# cable-adapter-24.net
KiCad netlist of a schematic drawn in EAGLE
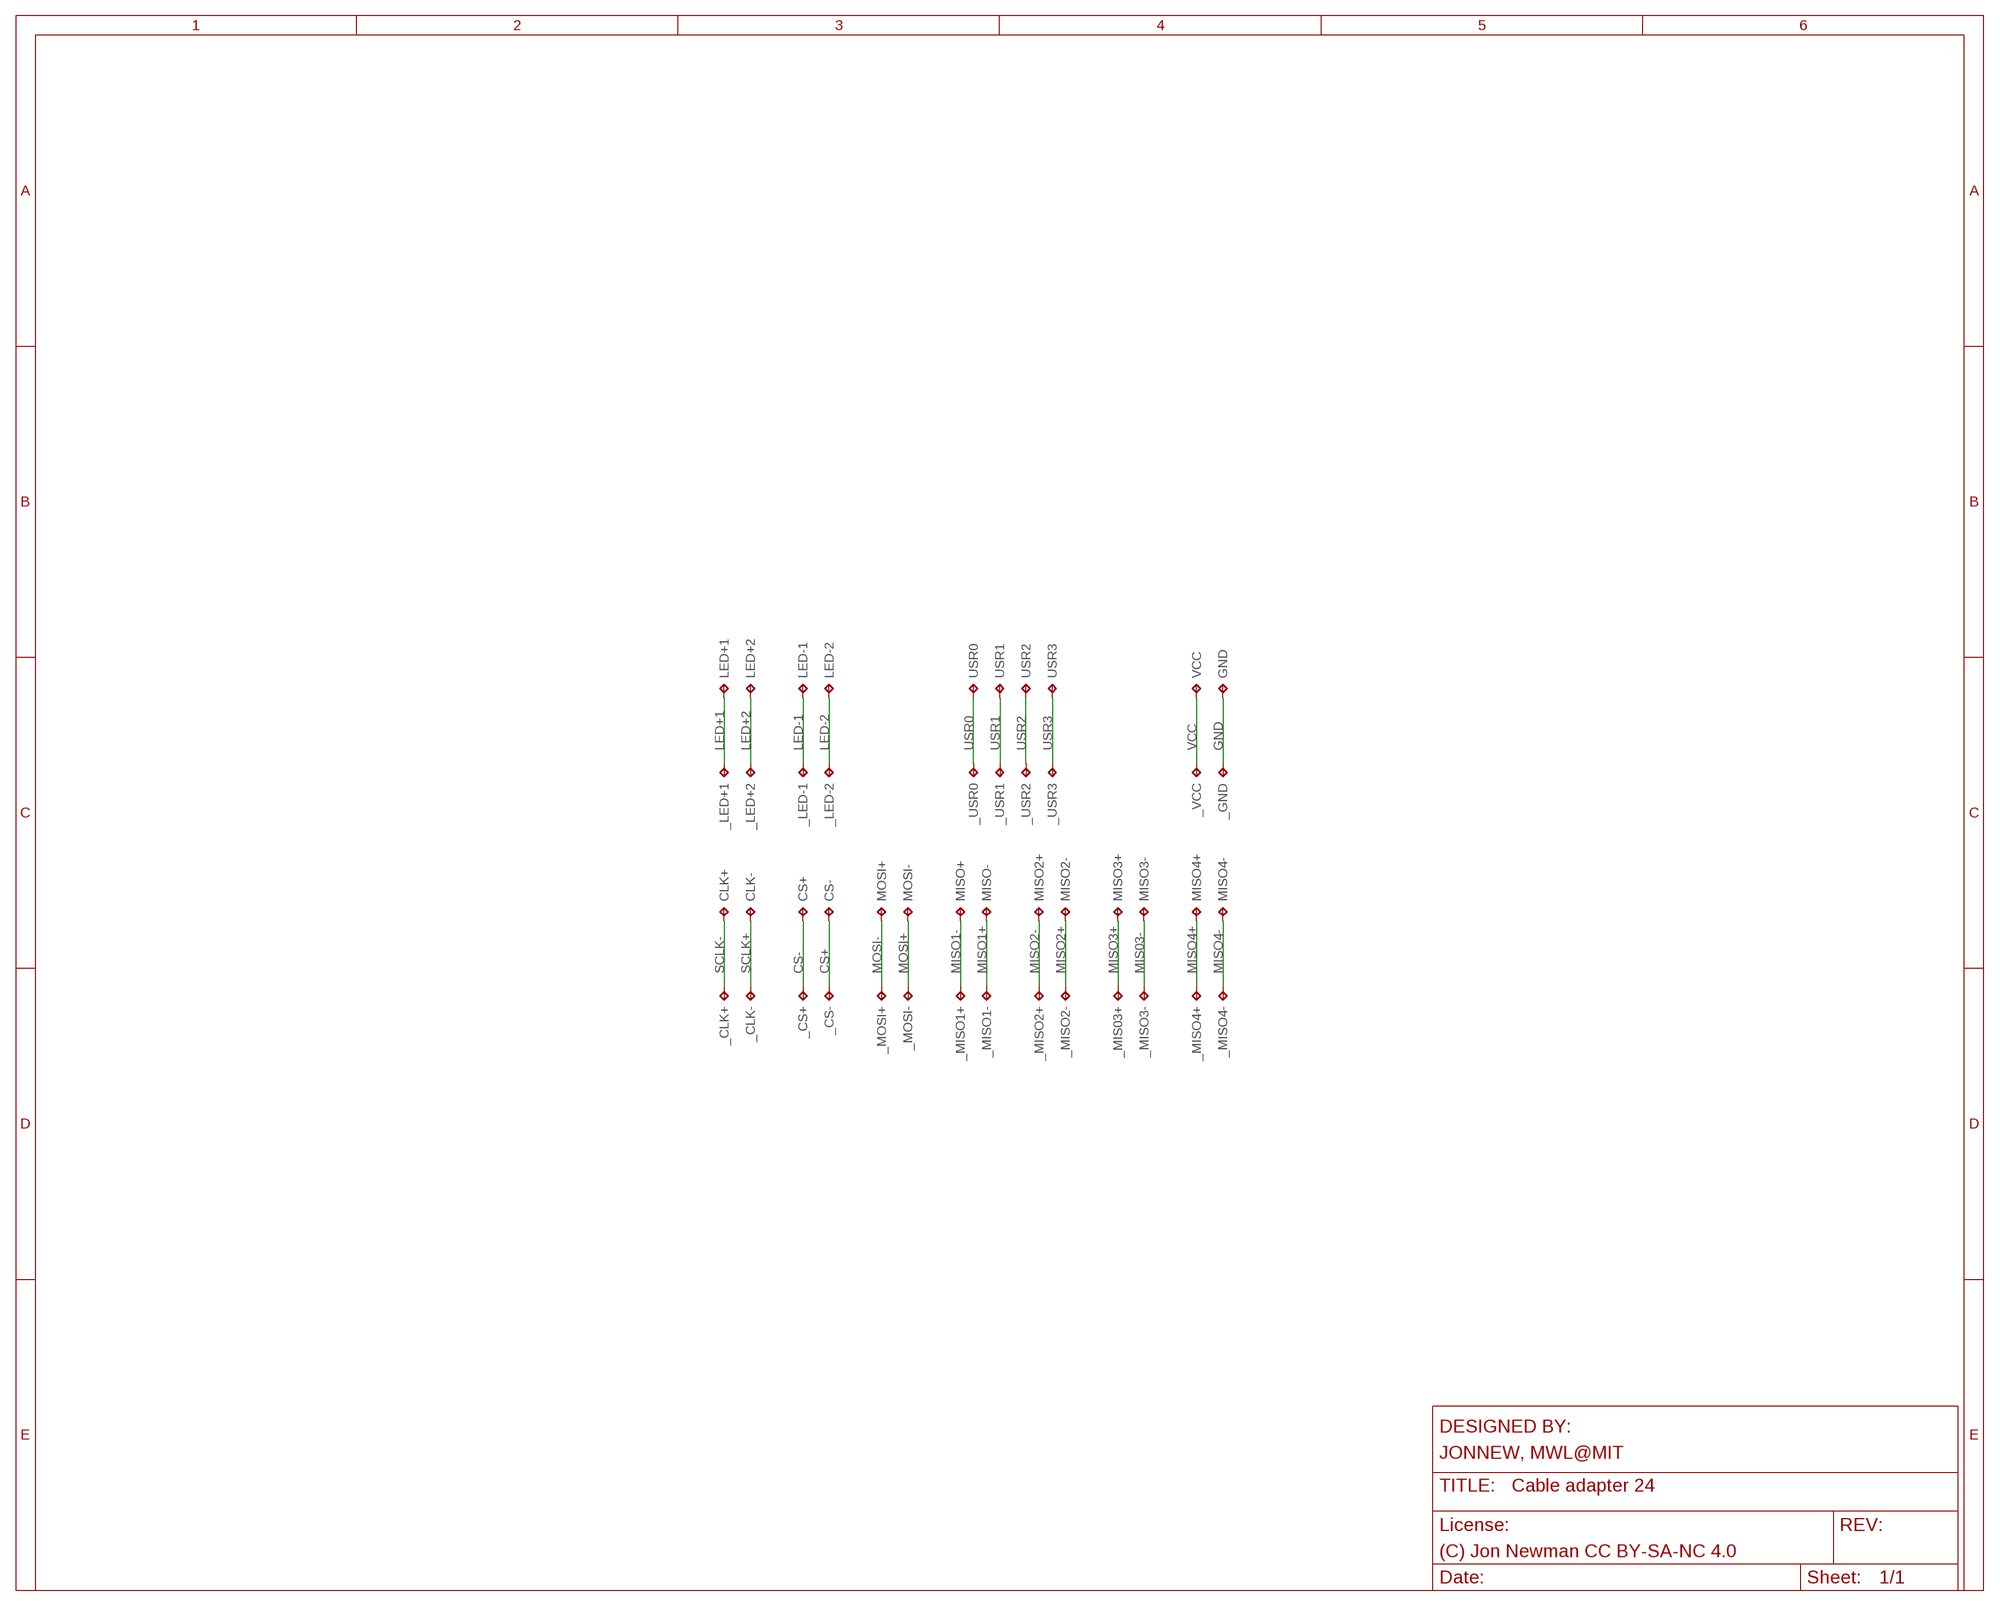
[diagram p0: schematic, sheet 1]

(export (version "E")
  (design (tool "Eeschema 10.0.6"))
  (components
    (comp (ref "CLK+")
      (value "TP_SPI_WIRE+")
      (footprint "eagle-import:SPI_WIRE+")
      (libsource (lib "eagle-import") (part "TP_SPI_WIRE+"))
    )
    (comp (ref "CLK-")
      (value "TP_SPI_WIRE+")
      (footprint "eagle-import:SPI_WIRE+")
      (libsource (lib "eagle-import") (part "TP_SPI_WIRE+"))
    )
    (comp (ref "CS+")
      (value "TP_SPI_WIRE+")
      (footprint "eagle-import:SPI_WIRE+")
      (libsource (lib "eagle-import") (part "TP_SPI_WIRE+"))
    )
    (comp (ref "CS-")
      (value "TP_SPI_WIRE+")
      (footprint "eagle-import:SPI_WIRE+")
      (libsource (lib "eagle-import") (part "TP_SPI_WIRE+"))
    )
    (comp (ref "GND")
      (value "TP_SPI_WIRE+")
      (footprint "eagle-import:SPI_WIRE+")
      (libsource (lib "eagle-import") (part "TP_SPI_WIRE+"))
    )
    (comp (ref "LED+1")
      (value "TP_SPI_WIRE+")
      (footprint "eagle-import:SPI_WIRE+")
      (libsource (lib "eagle-import") (part "TP_SPI_WIRE+"))
    )
    (comp (ref "LED+2")
      (value "TP_SPI_WIRE+")
      (footprint "eagle-import:SPI_WIRE+")
      (libsource (lib "eagle-import") (part "TP_SPI_WIRE+"))
    )
    (comp (ref "LED-1")
      (value "TP_SPI_WIRE+")
      (footprint "eagle-import:SPI_WIRE+")
      (libsource (lib "eagle-import") (part "TP_SPI_WIRE+"))
    )
    (comp (ref "LED-2")
      (value "TP_SPI_WIRE+")
      (footprint "eagle-import:SPI_WIRE+")
      (libsource (lib "eagle-import") (part "TP_SPI_WIRE+"))
    )
    (comp (ref "MISO+")
      (value "TP_SPI_WIRE+")
      (footprint "eagle-import:SPI_WIRE+")
      (libsource (lib "eagle-import") (part "TP_SPI_WIRE+"))
    )
    (comp (ref "MISO-")
      (value "TP_SPI_WIRE+")
      (footprint "eagle-import:SPI_WIRE+")
      (libsource (lib "eagle-import") (part "TP_SPI_WIRE+"))
    )
    (comp (ref "MISO2+")
      (value "TP_SPI_WIRE+")
      (footprint "eagle-import:SPI_WIRE+")
      (libsource (lib "eagle-import") (part "TP_SPI_WIRE+"))
    )
    (comp (ref "MISO2-")
      (value "TP_SPI_WIRE+")
      (footprint "eagle-import:SPI_WIRE+")
      (libsource (lib "eagle-import") (part "TP_SPI_WIRE+"))
    )
    (comp (ref "MISO3+")
      (value "TP_SPI_WIRE+")
      (footprint "eagle-import:SPI_WIRE+")
      (libsource (lib "eagle-import") (part "TP_SPI_WIRE+"))
    )
    (comp (ref "MISO3-")
      (value "TP_SPI_WIRE+")
      (footprint "eagle-import:SPI_WIRE+")
      (libsource (lib "eagle-import") (part "TP_SPI_WIRE+"))
    )
    (comp (ref "MISO4+")
      (value "TP_SPI_WIRE+")
      (footprint "eagle-import:SPI_WIRE+")
      (libsource (lib "eagle-import") (part "TP_SPI_WIRE+"))
    )
    (comp (ref "MISO4-")
      (value "TP_SPI_WIRE+")
      (footprint "eagle-import:SPI_WIRE+")
      (libsource (lib "eagle-import") (part "TP_SPI_WIRE+"))
    )
    (comp (ref "MOSI+")
      (value "TP_SPI_WIRE+")
      (footprint "eagle-import:SPI_WIRE+")
      (libsource (lib "eagle-import") (part "TP_SPI_WIRE+"))
    )
    (comp (ref "MOSI-")
      (value "TP_SPI_WIRE+")
      (footprint "eagle-import:SPI_WIRE+")
      (libsource (lib "eagle-import") (part "TP_SPI_WIRE+"))
    )
    (comp (ref "USR0")
      (value "TP_SPI_WIRE+")
      (footprint "eagle-import:SPI_WIRE+")
      (libsource (lib "eagle-import") (part "TP_SPI_WIRE+"))
    )
    (comp (ref "USR1")
      (value "TP_SPI_WIRE+")
      (footprint "eagle-import:SPI_WIRE+")
      (libsource (lib "eagle-import") (part "TP_SPI_WIRE+"))
    )
    (comp (ref "USR2")
      (value "TP_SPI_WIRE+")
      (footprint "eagle-import:SPI_WIRE+")
      (libsource (lib "eagle-import") (part "TP_SPI_WIRE+"))
    )
    (comp (ref "USR3")
      (value "TP_SPI_WIRE+")
      (footprint "eagle-import:SPI_WIRE+")
      (libsource (lib "eagle-import") (part "TP_SPI_WIRE+"))
    )
    (comp (ref "VCC")
      (value "TP_SPI_WIRE+")
      (footprint "eagle-import:SPI_WIRE+")
      (libsource (lib "eagle-import") (part "TP_SPI_WIRE+"))
    )
    (comp (ref "_CLK+")
      (value "TP_SPI_WIRE+")
      (footprint "eagle-import:SPI_WIRE+")
      (libsource (lib "eagle-import") (part "TP_SPI_WIRE+"))
    )
    (comp (ref "_CLK-")
      (value "TP_SPI_WIRE+")
      (footprint "eagle-import:SPI_WIRE+")
      (libsource (lib "eagle-import") (part "TP_SPI_WIRE+"))
    )
    (comp (ref "_CS+")
      (value "TP_SPI_WIRE+")
      (footprint "eagle-import:SPI_WIRE+")
      (libsource (lib "eagle-import") (part "TP_SPI_WIRE+"))
    )
    (comp (ref "_CS-")
      (value "TP_SPI_WIRE+")
      (footprint "eagle-import:SPI_WIRE+")
      (libsource (lib "eagle-import") (part "TP_SPI_WIRE+"))
    )
    (comp (ref "_GND")
      (value "TP_SPI_WIRE+")
      (footprint "eagle-import:SPI_WIRE+")
      (libsource (lib "eagle-import") (part "TP_SPI_WIRE+"))
    )
    (comp (ref "_LED+1")
      (value "TP_SPI_WIRE+")
      (footprint "eagle-import:SPI_WIRE+")
      (libsource (lib "eagle-import") (part "TP_SPI_WIRE+"))
    )
    (comp (ref "_LED+2")
      (value "TP_SPI_WIRE+")
      (footprint "eagle-import:SPI_WIRE+")
      (libsource (lib "eagle-import") (part "TP_SPI_WIRE+"))
    )
    (comp (ref "_LED-1")
      (value "TP_SPI_WIRE+")
      (footprint "eagle-import:SPI_WIRE+")
      (libsource (lib "eagle-import") (part "TP_SPI_WIRE+"))
    )
    (comp (ref "_LED-2")
      (value "TP_SPI_WIRE+")
      (footprint "eagle-import:SPI_WIRE+")
      (libsource (lib "eagle-import") (part "TP_SPI_WIRE+"))
    )
    (comp (ref "_MIS03+")
      (value "TP_SPI_WIRE+")
      (footprint "eagle-import:SPI_WIRE+")
      (libsource (lib "eagle-import") (part "TP_SPI_WIRE+"))
    )
    (comp (ref "_MISO1+")
      (value "TP_SPI_WIRE+")
      (footprint "eagle-import:SPI_WIRE+")
      (libsource (lib "eagle-import") (part "TP_SPI_WIRE+"))
    )
    (comp (ref "_MISO1-")
      (value "TP_SPI_WIRE+")
      (footprint "eagle-import:SPI_WIRE+")
      (libsource (lib "eagle-import") (part "TP_SPI_WIRE+"))
    )
    (comp (ref "_MISO2+")
      (value "TP_SPI_WIRE+")
      (footprint "eagle-import:SPI_WIRE+")
      (libsource (lib "eagle-import") (part "TP_SPI_WIRE+"))
    )
    (comp (ref "_MISO2-")
      (value "TP_SPI_WIRE+")
      (footprint "eagle-import:SPI_WIRE+")
      (libsource (lib "eagle-import") (part "TP_SPI_WIRE+"))
    )
    (comp (ref "_MISO3-")
      (value "MISO3+")
      (footprint "eagle-import:SPI_WIRE+")
      (libsource (lib "eagle-import") (part "TP_SPI_WIRE+"))
    )
    (comp (ref "_MISO4+")
      (value "TP_SPI_WIRE+")
      (footprint "eagle-import:SPI_WIRE+")
      (libsource (lib "eagle-import") (part "TP_SPI_WIRE+"))
    )
    (comp (ref "_MISO4-")
      (value "TP_SPI_WIRE+")
      (footprint "eagle-import:SPI_WIRE+")
      (libsource (lib "eagle-import") (part "TP_SPI_WIRE+"))
    )
    (comp (ref "_MOSI+")
      (value "TP_SPI_WIRE+")
      (footprint "eagle-import:SPI_WIRE+")
      (libsource (lib "eagle-import") (part "TP_SPI_WIRE+"))
    )
    (comp (ref "_MOSI-")
      (value "TP_SPI_WIRE+")
      (footprint "eagle-import:SPI_WIRE+")
      (libsource (lib "eagle-import") (part "TP_SPI_WIRE+"))
    )
    (comp (ref "_USR0")
      (value "TP_SPI_WIRE+")
      (footprint "eagle-import:SPI_WIRE+")
      (libsource (lib "eagle-import") (part "TP_SPI_WIRE+"))
    )
    (comp (ref "_USR1")
      (value "TP_SPI_WIRE+")
      (footprint "eagle-import:SPI_WIRE+")
      (libsource (lib "eagle-import") (part "TP_SPI_WIRE+"))
    )
    (comp (ref "_USR2")
      (value "TP_SPI_WIRE+")
      (footprint "eagle-import:SPI_WIRE+")
      (libsource (lib "eagle-import") (part "TP_SPI_WIRE+"))
    )
    (comp (ref "_USR3")
      (value "TP_SPI_WIRE+")
      (footprint "eagle-import:SPI_WIRE+")
      (libsource (lib "eagle-import") (part "TP_SPI_WIRE+"))
    )
    (comp (ref "_VCC")
      (value "TP_SPI_WIRE+")
      (footprint "eagle-import:SPI_WIRE+")
      (libsource (lib "eagle-import") (part "TP_SPI_WIRE+"))
    )
  )
  (nets
    (net (code "1") (name "/CS+") (class "Default")
      (node (ref "CS-") (pin "P$1") (pinfunction "TP_P$1") (pintype "input"))
      (node (ref "_CS-") (pin "P$1") (pinfunction "TP_P$1") (pintype "input"))
    )
    (net (code "2") (name "/CS-") (class "Default")
      (node (ref "CS+") (pin "P$1") (pinfunction "TP_P$1") (pintype "input"))
      (node (ref "_CS+") (pin "P$1") (pinfunction "TP_P$1") (pintype "input"))
    )
    (net (code "3") (name "/GND") (class "Default")
      (node (ref "GND") (pin "P$1") (pinfunction "TP_P$1") (pintype "input"))
      (node (ref "_GND") (pin "P$1") (pinfunction "TP_P$1") (pintype "input"))
    )
    (net (code "4") (name "/LED+1") (class "Default")
      (node (ref "LED+1") (pin "P$1") (pinfunction "TP_P$1") (pintype "input"))
      (node (ref "_LED+1") (pin "P$1") (pinfunction "TP_P$1") (pintype "input"))
    )
    (net (code "5") (name "/LED+2") (class "Default")
      (node (ref "LED+2") (pin "P$1") (pinfunction "TP_P$1") (pintype "input"))
      (node (ref "_LED+2") (pin "P$1") (pinfunction "TP_P$1") (pintype "input"))
    )
    (net (code "6") (name "/LED-1") (class "Default")
      (node (ref "LED-1") (pin "P$1") (pinfunction "TP_P$1") (pintype "input"))
      (node (ref "_LED-1") (pin "P$1") (pinfunction "TP_P$1") (pintype "input"))
    )
    (net (code "7") (name "/LED-2") (class "Default")
      (node (ref "LED-2") (pin "P$1") (pinfunction "TP_P$1") (pintype "input"))
      (node (ref "_LED-2") (pin "P$1") (pinfunction "TP_P$1") (pintype "input"))
    )
    (net (code "8") (name "/MIS03-") (class "Default")
      (node (ref "MISO3-") (pin "P$1") (pinfunction "TP_P$1") (pintype "input"))
      (node (ref "_MISO3-") (pin "P$1") (pinfunction "TP_P$1") (pintype "input"))
    )
    (net (code "9") (name "/MISO1+") (class "Default")
      (node (ref "MISO-") (pin "P$1") (pinfunction "TP_P$1") (pintype "input"))
      (node (ref "_MISO1-") (pin "P$1") (pinfunction "TP_P$1") (pintype "input"))
    )
    (net (code "10") (name "/MISO1-") (class "Default")
      (node (ref "MISO+") (pin "P$1") (pinfunction "TP_P$1") (pintype "input"))
      (node (ref "_MISO1+") (pin "P$1") (pinfunction "TP_P$1") (pintype "input"))
    )
    (net (code "11") (name "/MISO2+") (class "Default")
      (node (ref "MISO2-") (pin "P$1") (pinfunction "TP_P$1") (pintype "input"))
      (node (ref "_MISO2-") (pin "P$1") (pinfunction "TP_P$1") (pintype "input"))
    )
    (net (code "12") (name "/MISO2-") (class "Default")
      (node (ref "MISO2+") (pin "P$1") (pinfunction "TP_P$1") (pintype "input"))
      (node (ref "_MISO2+") (pin "P$1") (pinfunction "TP_P$1") (pintype "input"))
    )
    (net (code "13") (name "/MISO3+") (class "Default")
      (node (ref "MISO3+") (pin "P$1") (pinfunction "TP_P$1") (pintype "input"))
      (node (ref "_MIS03+") (pin "P$1") (pinfunction "TP_P$1") (pintype "input"))
    )
    (net (code "14") (name "/MISO4+") (class "Default")
      (node (ref "MISO4+") (pin "P$1") (pinfunction "TP_P$1") (pintype "input"))
      (node (ref "_MISO4+") (pin "P$1") (pinfunction "TP_P$1") (pintype "input"))
    )
    (net (code "15") (name "/MISO4-") (class "Default")
      (node (ref "MISO4-") (pin "P$1") (pinfunction "TP_P$1") (pintype "input"))
      (node (ref "_MISO4-") (pin "P$1") (pinfunction "TP_P$1") (pintype "input"))
    )
    (net (code "16") (name "/MOSI+") (class "Default")
      (node (ref "MOSI-") (pin "P$1") (pinfunction "TP_P$1") (pintype "input"))
      (node (ref "_MOSI-") (pin "P$1") (pinfunction "TP_P$1") (pintype "input"))
    )
    (net (code "17") (name "/MOSI-") (class "Default")
      (node (ref "MOSI+") (pin "P$1") (pinfunction "TP_P$1") (pintype "input"))
      (node (ref "_MOSI+") (pin "P$1") (pinfunction "TP_P$1") (pintype "input"))
    )
    (net (code "18") (name "/SCLK+") (class "Default")
      (node (ref "CLK-") (pin "P$1") (pinfunction "TP_P$1") (pintype "input"))
      (node (ref "_CLK-") (pin "P$1") (pinfunction "TP_P$1") (pintype "input"))
    )
    (net (code "19") (name "/SCLK-") (class "Default")
      (node (ref "CLK+") (pin "P$1") (pinfunction "TP_P$1") (pintype "input"))
      (node (ref "_CLK+") (pin "P$1") (pinfunction "TP_P$1") (pintype "input"))
    )
    (net (code "20") (name "/USR0") (class "Default")
      (node (ref "USR0") (pin "P$1") (pinfunction "TP_P$1") (pintype "input"))
      (node (ref "_USR0") (pin "P$1") (pinfunction "TP_P$1") (pintype "input"))
    )
    (net (code "21") (name "/USR1") (class "Default")
      (node (ref "USR1") (pin "P$1") (pinfunction "TP_P$1") (pintype "input"))
      (node (ref "_USR1") (pin "P$1") (pinfunction "TP_P$1") (pintype "input"))
    )
    (net (code "22") (name "/USR2") (class "Default")
      (node (ref "USR2") (pin "P$1") (pinfunction "TP_P$1") (pintype "input"))
      (node (ref "_USR2") (pin "P$1") (pinfunction "TP_P$1") (pintype "input"))
    )
    (net (code "23") (name "/USR3") (class "Default")
      (node (ref "USR3") (pin "P$1") (pinfunction "TP_P$1") (pintype "input"))
      (node (ref "_USR3") (pin "P$1") (pinfunction "TP_P$1") (pintype "input"))
    )
    (net (code "24") (name "/VCC") (class "Default")
      (node (ref "VCC") (pin "P$1") (pinfunction "TP_P$1") (pintype "input"))
      (node (ref "_VCC") (pin "P$1") (pinfunction "TP_P$1") (pintype "input"))
    )
  )
)
